# CARDUINO_32U4.net
KiCad netlist of a schematic drawn in EAGLE
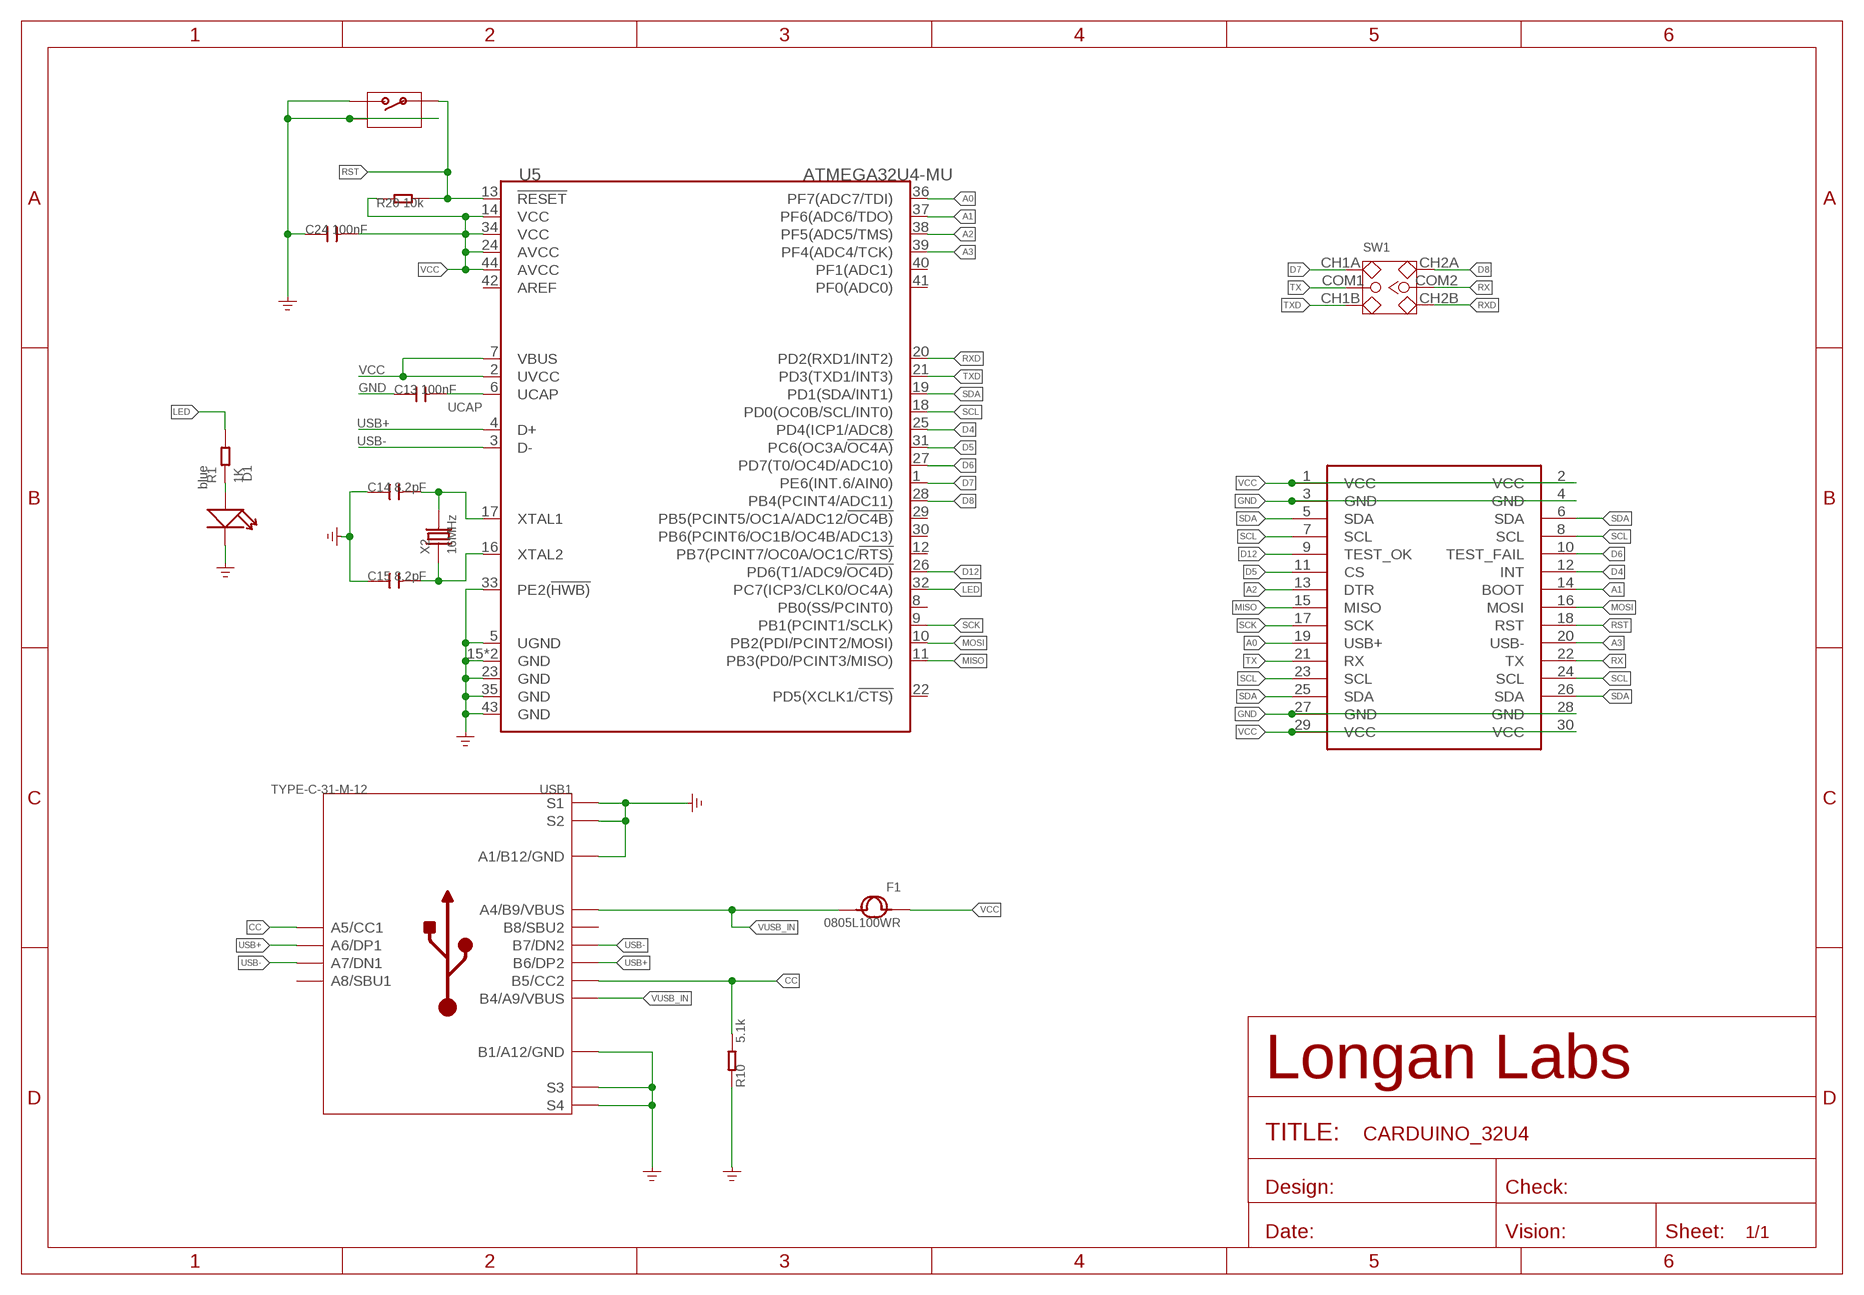
[diagram p0: schematic, sheet 1]

(export (version "E")
  (design (tool "Eeschema 10.0.6"))
  (components
    (comp (ref "C13")
      (value "100nF")
      (footprint "eagle-import:C0603")
      (libsource (lib "eagle-import") (part "C-0603"))
    )
    (comp (ref "C14")
      (value "8.2pF")
      (footprint "eagle-import:C0603")
      (libsource (lib "eagle-import") (part "C-0603"))
    )
    (comp (ref "C15")
      (value "8.2pF")
      (footprint "eagle-import:C0603")
      (libsource (lib "eagle-import") (part "C-0603"))
    )
    (comp (ref "C24")
      (value "100nF")
      (footprint "eagle-import:C0603")
      (libsource (lib "eagle-import") (part "C-0603"))
    )
    (comp (ref "D1")
      (value "blue")
      (footprint "eagle-import:LED-0603")
      (libsource (lib "eagle-import") (part "LED'0603'"))
    )
    (comp (ref "F1")
      (value "0805L100WR")
      (footprint "eagle-import:F0805")
      (libsource (lib "eagle-import") (part "FUSE0805"))
    )
    (comp (ref "MOUDLE1")
      (value "MOUDLE-2X15P-2.54'BOARD'")
      (footprint "eagle-import:MOUDLE-2X15P-2.54")
      (libsource (lib "eagle-import") (part "MOUDLE-2X15P-2.54'BOARD'"))
    )
    (comp (ref "R1")
      (value "1K")
      (footprint "eagle-import:R0603")
      (libsource (lib "eagle-import") (part "RES-0603"))
    )
    (comp (ref "R10")
      (value "5.1k")
      (footprint "eagle-import:R0603")
      (libsource (lib "eagle-import") (part "RES-0603"))
    )
    (comp (ref "R20")
      (value "10k")
      (footprint "eagle-import:R0603")
      (libsource (lib "eagle-import") (part "R-0603"))
    )
    (comp (ref "RESET")
      (value "BUTTON-4P-REINFORCE")
      (footprint "eagle-import:4P-SMD-7X3.5X3.5H")
      (libsource (lib "eagle-import") (part "BUTTON-4P-REINFORCE'TS-1188E'"))
    )
    (comp (ref "SW1")
      (value "SWITCH-2CH-6P")
      (footprint "eagle-import:SW6-2.5-SMD-9.2X3.5X3.5MM")
      (libsource (lib "eagle-import") (part "SWITCH-2CH-6P"))
    )
    (comp (ref "U5")
      (value "ATMEGA32U4-MU")
      (footprint "eagle-import:QFN44")
      (libsource (lib "eagle-import") (part "ATMEGA32U4-MU"))
    )
    (comp (ref "USB1")
      (value "TYPE-C-31-M-12")
      (footprint "eagle-import:USB2.0-TYPE-C")
      (libsource (lib "eagle-import") (part "USB2.0-TYPE-C"))
    )
    (comp (ref "X2")
      (value "16MHz")
      (footprint "eagle-import:2P-SMD-5X3.2")
      (libsource (lib "eagle-import") (part "CRYSTAL'5032'"))
    )
  )
  (nets
    (net (code "1") (name "/UCAP") (class "Default")
      (node (ref "C13") (pin "2") (pinfunction "2_2") (pintype "passive"))
      (node (ref "U5") (pin "6") (pinfunction "UCAP_6") (pintype "bidirectional"))
    )
    (net (code "2") (name "A0") (class "Default")
      (node (ref "MOUDLE1") (pin "19") (pinfunction "USB+_19") (pintype "bidirectional"))
      (node (ref "U5") (pin "36") (pinfunction "PF7(ADC7/TDI)_36") (pintype "bidirectional"))
    )
    (net (code "3") (name "A1") (class "Default")
      (node (ref "MOUDLE1") (pin "14") (pinfunction "BOOT_14") (pintype "bidirectional"))
      (node (ref "U5") (pin "37") (pinfunction "PF6(ADC6/TDO)_37") (pintype "bidirectional"))
    )
    (net (code "4") (name "A2") (class "Default")
      (node (ref "MOUDLE1") (pin "13") (pinfunction "DTR_13") (pintype "bidirectional"))
      (node (ref "U5") (pin "38") (pinfunction "PF5(ADC5/TMS)_38") (pintype "bidirectional"))
    )
    (net (code "5") (name "A3") (class "Default")
      (node (ref "MOUDLE1") (pin "20") (pinfunction "USB-_20") (pintype "bidirectional"))
      (node (ref "U5") (pin "39") (pinfunction "PF4(ADC4/TCK)_39") (pintype "bidirectional"))
    )
    (net (code "6") (name "CC") (class "Default")
      (node (ref "R10") (pin "2") (pinfunction "2_2") (pintype "passive"))
      (node (ref "USB1") (pin "A5") (pinfunction "A5/CC1_A5") (pintype "bidirectional"))
      (node (ref "USB1") (pin "B5") (pinfunction "B5/CC2_B5") (pintype "bidirectional"))
    )
    (net (code "7") (name "D4") (class "Default")
      (node (ref "MOUDLE1") (pin "12") (pinfunction "INT_12") (pintype "bidirectional"))
      (node (ref "U5") (pin "25") (pinfunction "PD4(ICP1/ADC8)_25") (pintype "bidirectional"))
    )
    (net (code "8") (name "D5") (class "Default")
      (node (ref "MOUDLE1") (pin "11") (pinfunction "CS_11") (pintype "bidirectional"))
      (node (ref "U5") (pin "31") (pinfunction "PC6(OC3A/~{OC4A})_31") (pintype "bidirectional"))
    )
    (net (code "9") (name "D6") (class "Default")
      (node (ref "MOUDLE1") (pin "10") (pinfunction "TEST_FAIL_10") (pintype "bidirectional"))
      (node (ref "U5") (pin "27") (pinfunction "PD7(T0/OC4D/ADC10)_27") (pintype "bidirectional"))
    )
    (net (code "10") (name "D7") (class "Default")
      (node (ref "SW1") (pin "CH1A") (pinfunction "CH1A_CH1A") (pintype "bidirectional"))
      (node (ref "U5") (pin "1") (pinfunction "PE6(INT.6/AIN0)_1") (pintype "bidirectional"))
    )
    (net (code "11") (name "D8") (class "Default")
      (node (ref "SW1") (pin "CH2A") (pinfunction "CH2A_CH2A") (pintype "bidirectional"))
      (node (ref "U5") (pin "28") (pinfunction "PB4(PCINT4/ADC11)_28") (pintype "bidirectional"))
    )
    (net (code "12") (name "D12") (class "Default")
      (node (ref "MOUDLE1") (pin "9") (pinfunction "TEST_OK_9") (pintype "bidirectional"))
      (node (ref "U5") (pin "26") (pinfunction "PD6(T1/ADC9/~{OC4D})_26") (pintype "bidirectional"))
    )
    (net (code "13") (name "GND") (class "Default")
      (node (ref "C13") (pin "1") (pinfunction "1_1") (pintype "passive"))
      (node (ref "C14") (pin "1") (pinfunction "1_1") (pintype "passive"))
      (node (ref "C15") (pin "1") (pinfunction "1_1") (pintype "passive"))
      (node (ref "C24") (pin "1") (pinfunction "1_1") (pintype "passive"))
      (node (ref "D1") (pin "-") (pinfunction "-_-") (pintype "passive"))
      (node (ref "MOUDLE1") (pin "27") (pinfunction "GND_27") (pintype "bidirectional"))
      (node (ref "MOUDLE1") (pin "28") (pinfunction "GND_28") (pintype "bidirectional"))
      (node (ref "MOUDLE1") (pin "3") (pinfunction "GND_3") (pintype "bidirectional"))
      (node (ref "MOUDLE1") (pin "4") (pinfunction "GND_4") (pintype "bidirectional"))
      (node (ref "R10") (pin "1") (pinfunction "1_1") (pintype "passive"))
      (node (ref "RESET") (pin "2") (pinfunction "2_2") (pintype "bidirectional"))
      (node (ref "RESET") (pin "S1") (pinfunction "S1_S1") (pintype "bidirectional"))
      (node (ref "RESET") (pin "S2") (pinfunction "S2_S2") (pintype "bidirectional"))
      (node (ref "U5") (pin "15") (pinfunction "GND_15") (pintype "bidirectional"))
      (node (ref "U5") (pin "23") (pinfunction "GND_23") (pintype "bidirectional"))
      (node (ref "U5") (pin "33") (pinfunction "PE2(~{HWB})_33") (pintype "bidirectional"))
      (node (ref "U5") (pin "35") (pinfunction "GND_35") (pintype "bidirectional"))
      (node (ref "U5") (pin "43") (pinfunction "GND_43") (pintype "bidirectional"))
      (node (ref "U5") (pin "5") (pinfunction "UGND_5") (pintype "bidirectional"))
      (node (ref "U5") (pin "TAB") (pinfunction "GND_TAB") (pintype "bidirectional"))
      (node (ref "USB1") (pin "A1_B12") (pinfunction "A1/B12/GND_A1_B12") (pintype "bidirectional"))
      (node (ref "USB1") (pin "B1_A12") (pinfunction "B1/A12/GND_B1_A12") (pintype "bidirectional"))
      (node (ref "USB1") (pin "S1") (pinfunction "S1_S1") (pintype "bidirectional"))
      (node (ref "USB1") (pin "S2") (pinfunction "S2_S2") (pintype "bidirectional"))
      (node (ref "USB1") (pin "S3") (pinfunction "S3_S3") (pintype "bidirectional"))
      (node (ref "USB1") (pin "S4") (pinfunction "S4_S4") (pintype "bidirectional"))
      (node (ref "USB1") (pin "S5") (pinfunction "S1_S5") (pintype "bidirectional"))
      (node (ref "USB1") (pin "S6") (pinfunction "S2_S6") (pintype "bidirectional"))
    )
    (net (code "14") (name "LED") (class "Default")
      (node (ref "R1") (pin "2") (pinfunction "2_2") (pintype "passive"))
      (node (ref "U5") (pin "32") (pinfunction "PC7(ICP3/CLK0/OC4A)_32") (pintype "bidirectional"))
    )
    (net (code "15") (name "MISO") (class "Default")
      (node (ref "MOUDLE1") (pin "15") (pinfunction "MISO_15") (pintype "bidirectional"))
      (node (ref "U5") (pin "11") (pinfunction "PB3(PD0/PCINT3/MISO)_11") (pintype "bidirectional"))
    )
    (net (code "16") (name "MOSI") (class "Default")
      (node (ref "MOUDLE1") (pin "16") (pinfunction "MOSI_16") (pintype "bidirectional"))
      (node (ref "U5") (pin "10") (pinfunction "PB2(PDI/PCINT2/MOSI)_10") (pintype "bidirectional"))
    )
    (net (code "17") (name "Net-(D1-Pad+)") (class "Default")
      (node (ref "D1") (pin "+") (pinfunction "+_+") (pintype "passive"))
      (node (ref "R1") (pin "1") (pinfunction "1_1") (pintype "passive"))
    )
    (net (code "18") (name "Net-(U5-XTAL1)") (class "Default")
      (node (ref "C14") (pin "2") (pinfunction "2_2") (pintype "passive"))
      (node (ref "U5") (pin "17") (pinfunction "XTAL1_17") (pintype "bidirectional"))
      (node (ref "X2") (pin "2") (pinfunction "2_2") (pintype "passive"))
    )
    (net (code "19") (name "Net-(U5-XTAL2)") (class "Default")
      (node (ref "C15") (pin "2") (pinfunction "2_2") (pintype "passive"))
      (node (ref "U5") (pin "16") (pinfunction "XTAL2_16") (pintype "bidirectional"))
      (node (ref "X2") (pin "1") (pinfunction "1_1") (pintype "passive"))
    )
    (net (code "20") (name "RST") (class "Default")
      (node (ref "MOUDLE1") (pin "18") (pinfunction "RST_18") (pintype "bidirectional"))
      (node (ref "R20") (pin "2") (pinfunction "2_2") (pintype "passive"))
      (node (ref "RESET") (pin "1") (pinfunction "1_1") (pintype "bidirectional"))
      (node (ref "U5") (pin "13") (pinfunction "~{RESET}_13") (pintype "bidirectional"))
    )
    (net (code "21") (name "RX") (class "Default")
      (node (ref "MOUDLE1") (pin "22") (pinfunction "TX_22") (pintype "bidirectional"))
      (node (ref "SW1") (pin "COM2") (pinfunction "COM2_COM2") (pintype "bidirectional"))
    )
    (net (code "22") (name "RXD") (class "Default")
      (node (ref "SW1") (pin "CH2B") (pinfunction "CH2B_CH2B") (pintype "bidirectional"))
      (node (ref "U5") (pin "20") (pinfunction "PD2(RXD1/INT2)_20") (pintype "bidirectional"))
    )
    (net (code "23") (name "SCK") (class "Default")
      (node (ref "MOUDLE1") (pin "17") (pinfunction "SCK_17") (pintype "bidirectional"))
      (node (ref "U5") (pin "9") (pinfunction "PB1(PCINT1/SCLK)_9") (pintype "bidirectional"))
    )
    (net (code "24") (name "SCL") (class "Default")
      (node (ref "MOUDLE1") (pin "23") (pinfunction "SCL_23") (pintype "bidirectional"))
      (node (ref "MOUDLE1") (pin "24") (pinfunction "SCL_24") (pintype "bidirectional"))
      (node (ref "MOUDLE1") (pin "7") (pinfunction "SCL_7") (pintype "bidirectional"))
      (node (ref "MOUDLE1") (pin "8") (pinfunction "SCL_8") (pintype "bidirectional"))
      (node (ref "U5") (pin "18") (pinfunction "PD0(OC0B/SCL/INT0)_18") (pintype "bidirectional"))
    )
    (net (code "25") (name "SDA") (class "Default")
      (node (ref "MOUDLE1") (pin "25") (pinfunction "SDA_25") (pintype "bidirectional"))
      (node (ref "MOUDLE1") (pin "26") (pinfunction "SDA_26") (pintype "bidirectional"))
      (node (ref "MOUDLE1") (pin "5") (pinfunction "SDA_5") (pintype "bidirectional"))
      (node (ref "MOUDLE1") (pin "6") (pinfunction "SDA_6") (pintype "bidirectional"))
      (node (ref "U5") (pin "19") (pinfunction "PD1(SDA/INT1)_19") (pintype "bidirectional"))
    )
    (net (code "26") (name "TX") (class "Default")
      (node (ref "MOUDLE1") (pin "21") (pinfunction "RX_21") (pintype "bidirectional"))
      (node (ref "SW1") (pin "COM1") (pinfunction "COM1_COM1") (pintype "bidirectional"))
    )
    (net (code "27") (name "TXD") (class "Default")
      (node (ref "SW1") (pin "CH1B") (pinfunction "CH1B_CH1B") (pintype "bidirectional"))
      (node (ref "U5") (pin "21") (pinfunction "PD3(TXD1/INT3)_21") (pintype "bidirectional"))
    )
    (net (code "28") (name "USB+") (class "Default")
      (node (ref "U5") (pin "4") (pinfunction "D+_4") (pintype "bidirectional"))
      (node (ref "USB1") (pin "A6") (pinfunction "A6/DP1_A6") (pintype "bidirectional"))
      (node (ref "USB1") (pin "B6") (pinfunction "B6/DP2_B6") (pintype "bidirectional"))
    )
    (net (code "29") (name "USB-") (class "Default")
      (node (ref "U5") (pin "3") (pinfunction "D-_3") (pintype "bidirectional"))
      (node (ref "USB1") (pin "A7") (pinfunction "A7/DN1_A7") (pintype "bidirectional"))
      (node (ref "USB1") (pin "B7") (pinfunction "B7/DN2_B7") (pintype "bidirectional"))
    )
    (net (code "30") (name "VCC") (class "Default")
      (node (ref "C24") (pin "2") (pinfunction "2_2") (pintype "passive"))
      (node (ref "F1") (pin "1") (pinfunction "1_1") (pintype "bidirectional"))
      (node (ref "MOUDLE1") (pin "1") (pinfunction "VCC_1") (pintype "bidirectional"))
      (node (ref "MOUDLE1") (pin "2") (pinfunction "VCC_2") (pintype "bidirectional"))
      (node (ref "MOUDLE1") (pin "29") (pinfunction "VCC_29") (pintype "bidirectional"))
      (node (ref "MOUDLE1") (pin "30") (pinfunction "VCC_30") (pintype "bidirectional"))
      (node (ref "R20") (pin "1") (pinfunction "1_1") (pintype "passive"))
      (node (ref "U5") (pin "14") (pinfunction "VCC_14") (pintype "bidirectional"))
      (node (ref "U5") (pin "2") (pinfunction "UVCC_2") (pintype "bidirectional"))
      (node (ref "U5") (pin "24") (pinfunction "AVCC_24") (pintype "bidirectional"))
      (node (ref "U5") (pin "34") (pinfunction "VCC_34") (pintype "bidirectional"))
      (node (ref "U5") (pin "44") (pinfunction "AVCC_44") (pintype "bidirectional"))
      (node (ref "U5") (pin "7") (pinfunction "VBUS_7") (pintype "bidirectional"))
    )
    (net (code "31") (name "VUSB_IN") (class "Default")
      (node (ref "F1") (pin "2") (pinfunction "2_2") (pintype "bidirectional"))
      (node (ref "USB1") (pin "A4_B9") (pinfunction "A4/B9/VBUS_A4_B9") (pintype "bidirectional"))
      (node (ref "USB1") (pin "B4_A9") (pinfunction "B4/A9/VBUS_B4_A9") (pintype "bidirectional"))
    )
    (net (code "32") (name "unconnected-(U5-AREF-Pad42)") (class "Default")
      (node (ref "U5") (pin "42") (pinfunction "AREF_42") (pintype "bidirectional"))
    )
    (net (code "33") (name "unconnected-(U5-PB0(SS{slash}PCINT0)-Pad8)") (class "Default")
      (node (ref "U5") (pin "8") (pinfunction "PB0(SS/PCINT0)_8") (pintype "bidirectional"))
    )
    (net (code "34") (name "unconnected-(U5-PB5(PCINT5{slash}OC1A{slash}ADC12{slash}~{OC4B})-Pad29)") (class "Default")
      (node (ref "U5") (pin "29") (pinfunction "PB5(PCINT5/OC1A/ADC12/~{OC4B})_29") (pintype "bidirectional"))
    )
    (net (code "35") (name "unconnected-(U5-PB6(PCINT6{slash}OC1B{slash}OC4B{slash}ADC13)-Pad30)") (class "Default")
      (node (ref "U5") (pin "30") (pinfunction "PB6(PCINT6/OC1B/OC4B/ADC13)_30") (pintype "bidirectional"))
    )
    (net (code "36") (name "unconnected-(U5-PB7(PCINT7{slash}OC0A{slash}OC1C{slash}~{RTS})-Pad12)") (class "Default")
      (node (ref "U5") (pin "12") (pinfunction "PB7(PCINT7/OC0A/OC1C/~{RTS})_12") (pintype "bidirectional"))
    )
    (net (code "37") (name "unconnected-(U5-PD5(XCLK1{slash}~{CTS})-Pad22)") (class "Default")
      (node (ref "U5") (pin "22") (pinfunction "PD5(XCLK1/~{CTS})_22") (pintype "bidirectional"))
    )
    (net (code "38") (name "unconnected-(U5-PF0(ADC0)-Pad41)") (class "Default")
      (node (ref "U5") (pin "41") (pinfunction "PF0(ADC0)_41") (pintype "bidirectional"))
    )
    (net (code "39") (name "unconnected-(U5-PF1(ADC1)-Pad40)") (class "Default")
      (node (ref "U5") (pin "40") (pinfunction "PF1(ADC1)_40") (pintype "bidirectional"))
    )
    (net (code "40") (name "unconnected-(USB1-A8{slash}SBU1-PadA8)") (class "Default")
      (node (ref "USB1") (pin "A8") (pinfunction "A8/SBU1_A8") (pintype "bidirectional"))
    )
    (net (code "41") (name "unconnected-(USB1-B8{slash}SBU2-PadB8)") (class "Default")
      (node (ref "USB1") (pin "B8") (pinfunction "B8/SBU2_B8") (pintype "bidirectional"))
    )
  )
)
